# KSZ_-_ETH_HUB.net
KiCad netlist of a schematic drawn in Altium Designer
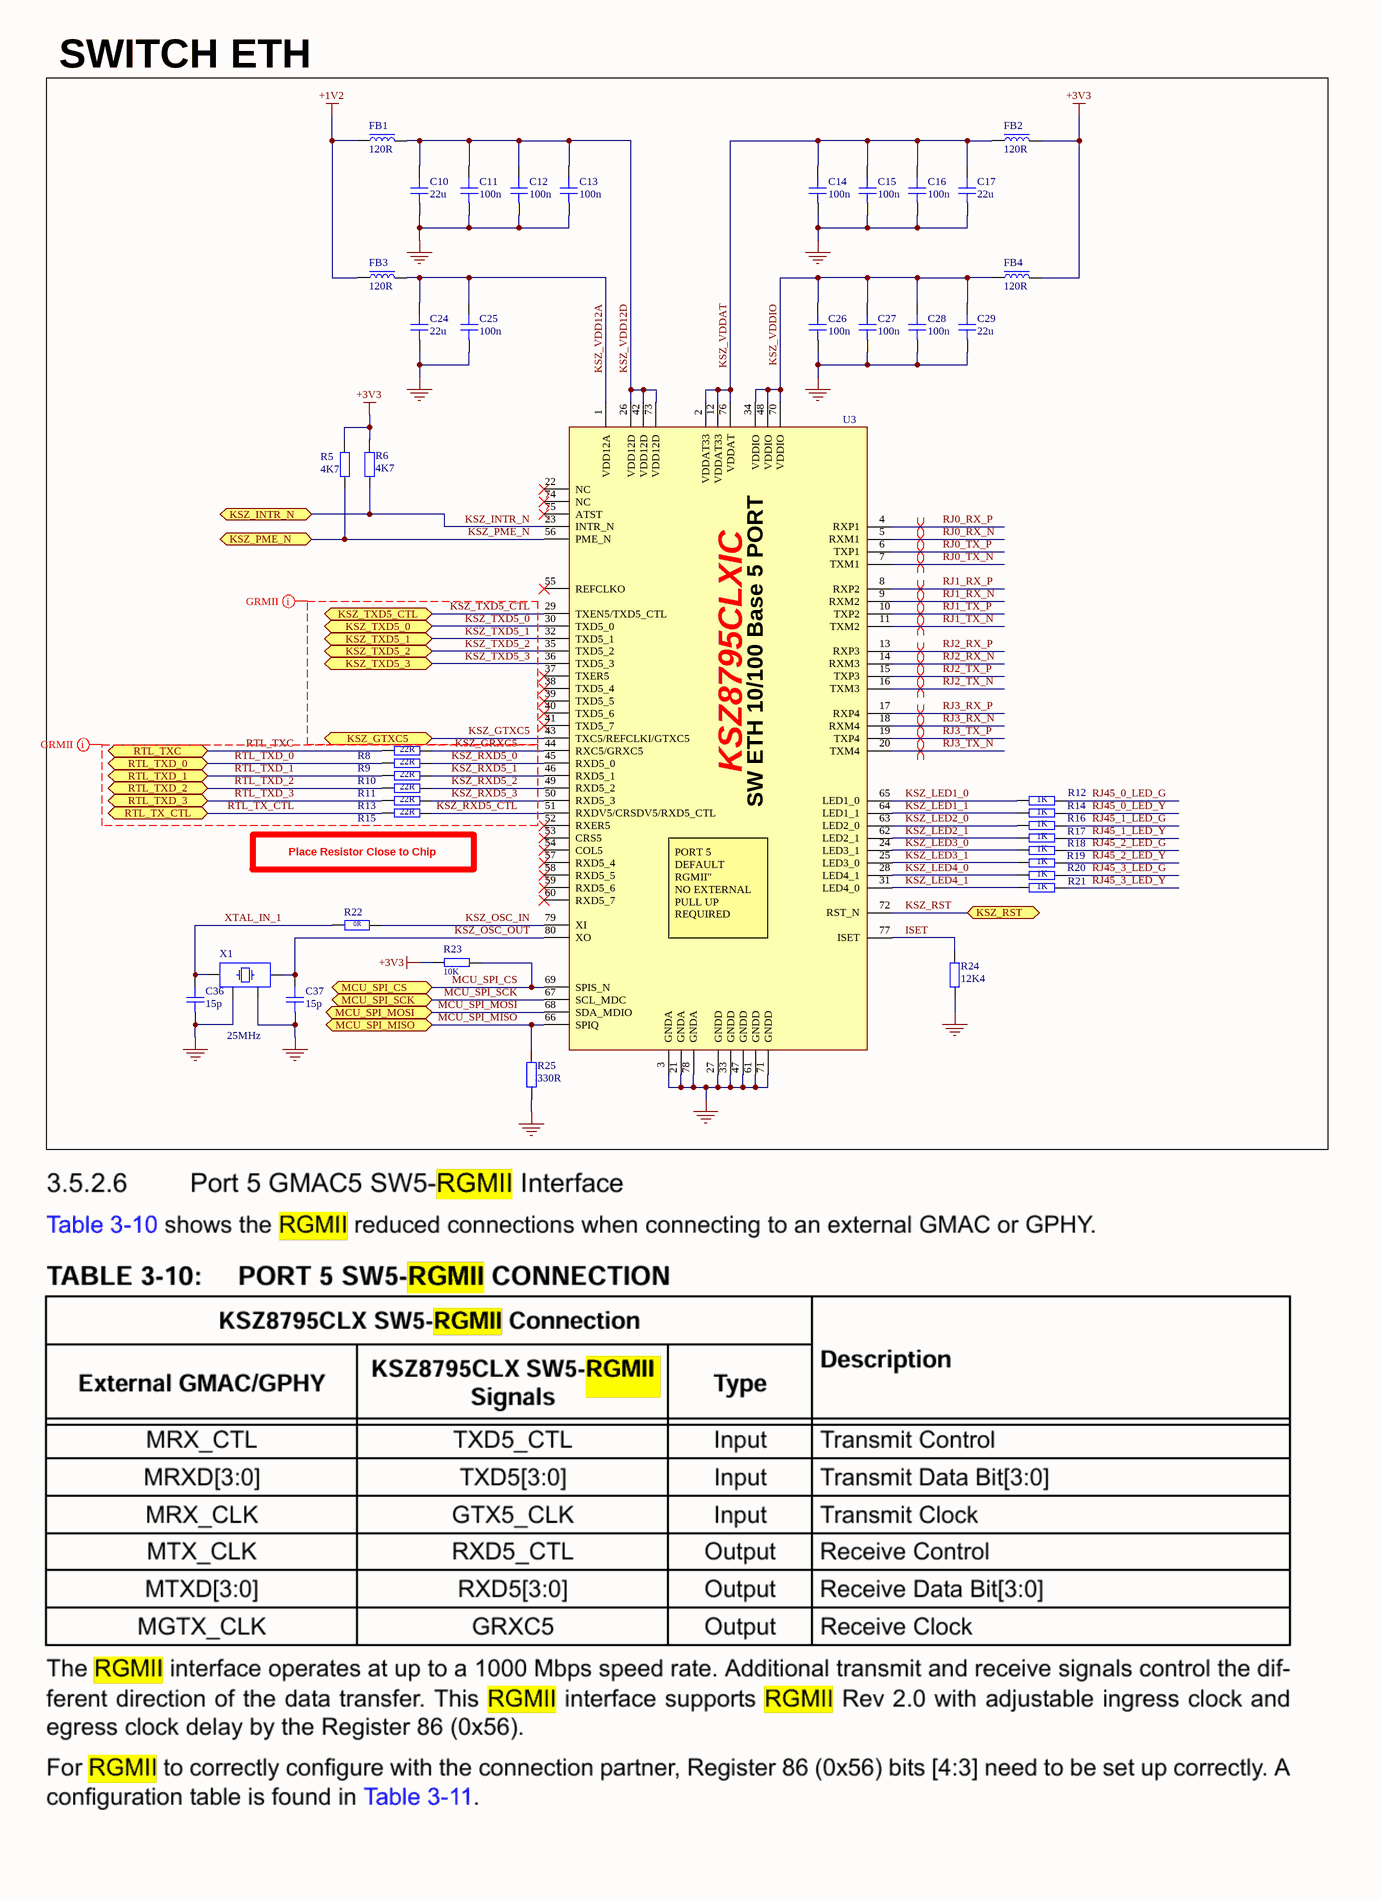
[diagram p0: KSZ - ETH HUB.SchDoc, left]
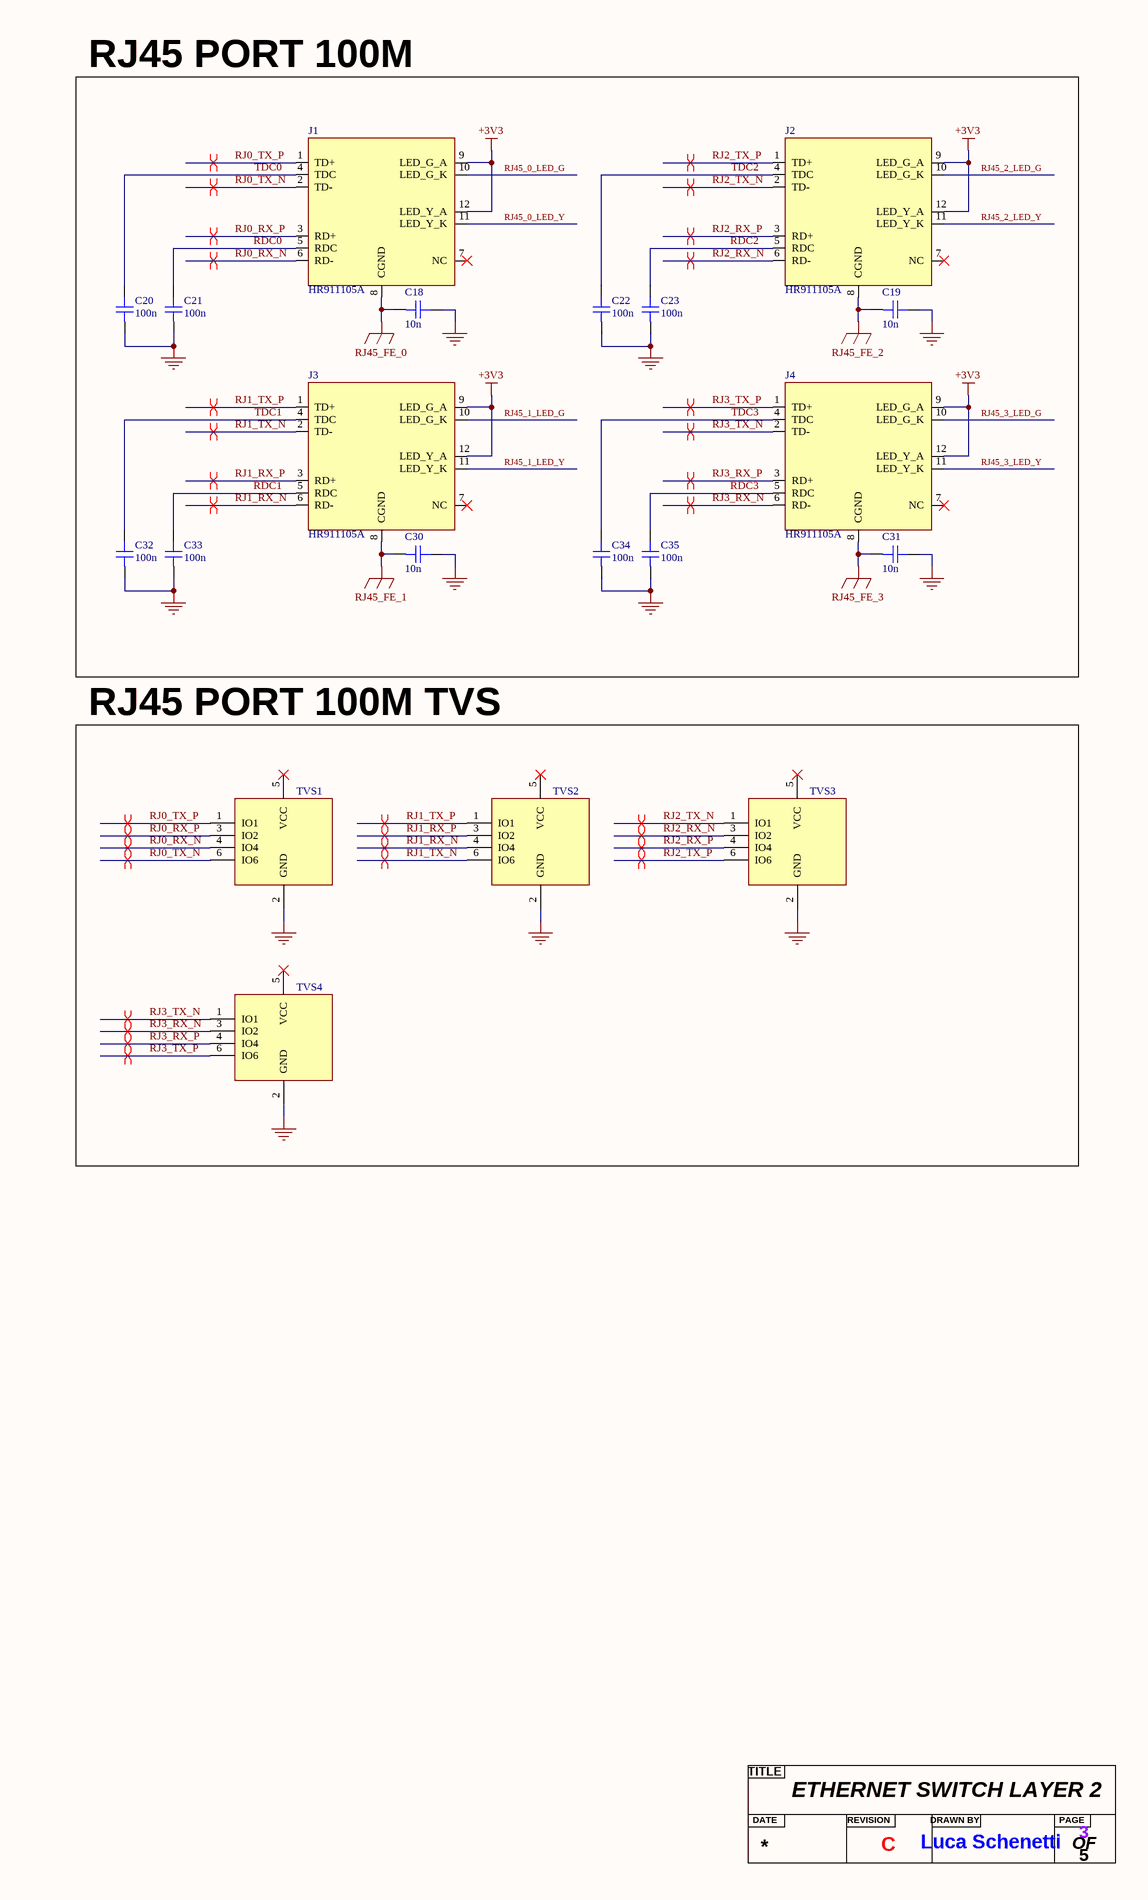
[diagram p1: KSZ - ETH HUB.SchDoc, right]

(export (version "E")
  (design (tool "Eeschema 10.0.6"))
  (components
    (comp (ref "C10")
      (value "22u")
      (footprint "CAP_0603")
      (description "Capacitor SMD 0603 [C59461]")
      (libsource (lib "Schematic-Lib-PhilsLab") (part "CAP_0603"))
    )
    (comp (ref "C11")
      (value "100n")
      (footprint "CAP_0603")
      (description "Capacitor SMD 0603 [C14663]")
      (libsource (lib "Schematic-Lib-PhilsLab") (part "CAP_0603"))
    )
    (comp (ref "C12")
      (value "100n")
      (footprint "CAP_0603")
      (description "Capacitor SMD 0603 [C14663]")
      (libsource (lib "Schematic-Lib-PhilsLab") (part "CAP_0603"))
    )
    (comp (ref "C13")
      (value "100n")
      (footprint "CAP_0603")
      (description "Capacitor SMD 0603 [C14663]")
      (libsource (lib "Schematic-Lib-PhilsLab") (part "CAP_0603"))
    )
    (comp (ref "C14")
      (value "100n")
      (footprint "CAP_0603")
      (description "Capacitor SMD 0603 [C14663]")
      (libsource (lib "Schematic-Lib-PhilsLab") (part "CAP_0603"))
    )
    (comp (ref "C15")
      (value "100n")
      (footprint "CAP_0603")
      (description "Capacitor SMD 0603 [C14663]")
      (libsource (lib "Schematic-Lib-PhilsLab") (part "CAP_0603"))
    )
    (comp (ref "C16")
      (value "100n")
      (footprint "CAP_0603")
      (description "Capacitor SMD 0603 [C14663]")
      (libsource (lib "Schematic-Lib-PhilsLab") (part "CAP_0603"))
    )
    (comp (ref "C17")
      (value "22u")
      (footprint "CAP_0603")
      (description "Capacitor SMD 0603 [C59461]")
      (libsource (lib "Schematic-Lib-PhilsLab") (part "CAP_0603"))
    )
    (comp (ref "C18")
      (value "10n")
      (footprint "CAP_1206")
      (description "[C1846]")
      (libsource (lib "Schematic-Lib-PhilsLab") (part "CAP_1206"))
    )
    (comp (ref "C19")
      (value "10n")
      (footprint "CAP_1206")
      (description "[C1846]")
      (libsource (lib "Schematic-Lib-PhilsLab") (part "CAP_1206"))
    )
    (comp (ref "C20")
      (value "100n")
      (footprint "CAP_0603")
      (description "Capacitor SMD 0603 [C14663]")
      (libsource (lib "Schematic-Lib-PhilsLab") (part "CAP_0603"))
    )
    (comp (ref "C21")
      (value "100n")
      (footprint "CAP_0603")
      (description "Capacitor SMD 0603 [C14663]")
      (libsource (lib "Schematic-Lib-PhilsLab") (part "CAP_0603"))
    )
    (comp (ref "C22")
      (value "100n")
      (footprint "CAP_0603")
      (description "Capacitor SMD 0603 [C14663]")
      (libsource (lib "Schematic-Lib-PhilsLab") (part "CAP_0603"))
    )
    (comp (ref "C23")
      (value "100n")
      (footprint "CAP_0603")
      (description "Capacitor SMD 0603 [C14663]")
      (libsource (lib "Schematic-Lib-PhilsLab") (part "CAP_0603"))
    )
    (comp (ref "C24")
      (value "22u")
      (footprint "CAP_0603")
      (description "Capacitor SMD 0603 [C59461]")
      (libsource (lib "Schematic-Lib-PhilsLab") (part "CAP_0603"))
    )
    (comp (ref "C25")
      (value "100n")
      (footprint "CAP_0603")
      (description "Capacitor SMD 0603 [C14663]")
      (libsource (lib "Schematic-Lib-PhilsLab") (part "CAP_0603"))
    )
    (comp (ref "C26")
      (value "100n")
      (footprint "CAP_0603")
      (description "Capacitor SMD 0603 [C14663]")
      (libsource (lib "Schematic-Lib-PhilsLab") (part "CAP_0603"))
    )
    (comp (ref "C27")
      (value "100n")
      (footprint "CAP_0603")
      (description "Capacitor SMD 0603 [C14663]")
      (libsource (lib "Schematic-Lib-PhilsLab") (part "CAP_0603"))
    )
    (comp (ref "C28")
      (value "100n")
      (footprint "CAP_0603")
      (description "Capacitor SMD 0603 [C14663]")
      (libsource (lib "Schematic-Lib-PhilsLab") (part "CAP_0603"))
    )
    (comp (ref "C29")
      (value "22u")
      (footprint "CAP_0603")
      (description "Capacitor SMD 0603 [C59461]")
      (libsource (lib "Schematic-Lib-PhilsLab") (part "CAP_0603"))
    )
    (comp (ref "C30")
      (value "10n")
      (footprint "CAP_1206")
      (description "[C1846]")
      (libsource (lib "Schematic-Lib-PhilsLab") (part "CAP_1206"))
    )
    (comp (ref "C31")
      (value "10n")
      (footprint "CAP_1206")
      (description "[C1846]")
      (libsource (lib "Schematic-Lib-PhilsLab") (part "CAP_1206"))
    )
    (comp (ref "C32")
      (value "100n")
      (footprint "CAP_0603")
      (description "Capacitor SMD 0603 [C14663]")
      (libsource (lib "Schematic-Lib-PhilsLab") (part "CAP_0603"))
    )
    (comp (ref "C33")
      (value "100n")
      (footprint "CAP_0603")
      (description "Capacitor SMD 0603 [C14663]")
      (libsource (lib "Schematic-Lib-PhilsLab") (part "CAP_0603"))
    )
    (comp (ref "C34")
      (value "100n")
      (footprint "CAP_0603")
      (description "Capacitor SMD 0603 [C14663]")
      (libsource (lib "Schematic-Lib-PhilsLab") (part "CAP_0603"))
    )
    (comp (ref "C35")
      (value "100n")
      (footprint "CAP_0603")
      (description "Capacitor SMD 0603 [C14663]")
      (libsource (lib "Schematic-Lib-PhilsLab") (part "CAP_0603"))
    )
    (comp (ref "C36")
      (value "15p")
      (footprint "CAP_0402")
      (description "Capacitor SMD 0402 [C1548]")
      (libsource (lib "Schematic-Lib-PhilsLab") (part "CAP_0402"))
    )
    (comp (ref "C37")
      (value "15p")
      (footprint "CAP_0402")
      (description "Capacitor SMD 0402 [C1548]")
      (libsource (lib "Schematic-Lib-PhilsLab") (part "CAP_0402"))
    )
    (comp (ref "FB1")
      (value "120R")
      (footprint "FB_0603")
      (description "Ferrite Bead SMD 0603[C76892]")
      (libsource (lib "Schematic-Lib-PhilsLab") (part "FB_0603"))
    )
    (comp (ref "FB2")
      (value "120R")
      (footprint "FB_0603")
      (description "Ferrite Bead SMD 0603[C76892]")
      (libsource (lib "Schematic-Lib-PhilsLab") (part "FB_0603"))
    )
    (comp (ref "FB3")
      (value "120R")
      (footprint "FB_0603")
      (description "Ferrite Bead SMD 0603[C76892]")
      (libsource (lib "Schematic-Lib-PhilsLab") (part "FB_0603"))
    )
    (comp (ref "FB4")
      (value "120R")
      (footprint "FB_0603")
      (description "Ferrite Bead SMD 0603[C76892]")
      (libsource (lib "Schematic-Lib-PhilsLab") (part "FB_0603"))
    )
    (comp (ref "J1")
      (value "HR911105A")
      (footprint "HR911105A")
      (description "Single Port RJ45 Connector w/ Integrated Magnetic and LED 10/100 Base-T [C12074]")
      (fields (field (name "MANUFACTURER") "HanRun"))
      (libsource (lib "Schematic-Lib-PhilsLab") (part "HR911105A"))
    )
    (comp (ref "J2")
      (value "HR911105A")
      (footprint "HR911105A")
      (description "Single Port RJ45 Connector w/ Integrated Magnetic and LED 10/100 Base-T [C12074]")
      (fields (field (name "MANUFACTURER") "HanRun"))
      (libsource (lib "Schematic-Lib-PhilsLab") (part "HR911105A"))
    )
    (comp (ref "J3")
      (value "HR911105A")
      (footprint "HR911105A")
      (description "Single Port RJ45 Connector w/ Integrated Magnetic and LED 10/100 Base-T [C12074]")
      (fields (field (name "MANUFACTURER") "HanRun"))
      (libsource (lib "Schematic-Lib-PhilsLab") (part "HR911105A"))
    )
    (comp (ref "J4")
      (value "HR911105A")
      (footprint "HR911105A")
      (description "Single Port RJ45 Connector w/ Integrated Magnetic and LED 10/100 Base-T [C12074]")
      (fields (field (name "MANUFACTURER") "HanRun"))
      (libsource (lib "Schematic-Lib-PhilsLab") (part "HR911105A"))
    )
    (comp (ref "R5")
      (value "4K7")
      (footprint "RES_0603")
      (description "[C23162]")
      (libsource (lib "Schematic-Lib-PhilsLab") (part "RES_0603"))
    )
    (comp (ref "R6")
      (value "4K7")
      (footprint "RES_0603")
      (description "[C23162]")
      (libsource (lib "Schematic-Lib-PhilsLab") (part "RES_0603"))
    )
    (comp (ref "R8")
      (value "22R")
      (footprint "RES_0402")
      (description "[C25092]")
      (libsource (lib "Schematic-Lib-PhilsLab") (part "RES_0402"))
    )
    (comp (ref "R9")
      (value "22R")
      (footprint "RES_0402")
      (description "[C25092]")
      (libsource (lib "Schematic-Lib-PhilsLab") (part "RES_0402"))
    )
    (comp (ref "R10")
      (value "22R")
      (footprint "RES_0402")
      (description "[C25092]")
      (libsource (lib "Schematic-Lib-PhilsLab") (part "RES_0402"))
    )
    (comp (ref "R11")
      (value "22R")
      (footprint "RES_0402")
      (description "[C25092]")
      (libsource (lib "Schematic-Lib-PhilsLab") (part "RES_0402"))
    )
    (comp (ref "R12")
      (value "1K")
      (footprint "RES_0603")
      (description "[C21190]")
      (libsource (lib "Schematic-Lib-PhilsLab") (part "RES_0603"))
    )
    (comp (ref "R13")
      (value "22R")
      (footprint "RES_0402")
      (description "[C25092]")
      (libsource (lib "Schematic-Lib-PhilsLab") (part "RES_0402"))
    )
    (comp (ref "R14")
      (value "1K")
      (footprint "RES_0603")
      (description "[C21190]")
      (libsource (lib "Schematic-Lib-PhilsLab") (part "RES_0603"))
    )
    (comp (ref "R15")
      (value "22R")
      (footprint "RES_0402")
      (description "[C25092]")
      (libsource (lib "Schematic-Lib-PhilsLab") (part "RES_0402"))
    )
    (comp (ref "R16")
      (value "1K")
      (footprint "RES_0603")
      (description "[C21190]")
      (libsource (lib "Schematic-Lib-PhilsLab") (part "RES_0603"))
    )
    (comp (ref "R17")
      (value "1K")
      (footprint "RES_0603")
      (description "[C21190]")
      (libsource (lib "Schematic-Lib-PhilsLab") (part "RES_0603"))
    )
    (comp (ref "R18")
      (value "1K")
      (footprint "RES_0603")
      (description "[C21190]")
      (libsource (lib "Schematic-Lib-PhilsLab") (part "RES_0603"))
    )
    (comp (ref "R19")
      (value "1K")
      (footprint "RES_0603")
      (description "[C21190]")
      (libsource (lib "Schematic-Lib-PhilsLab") (part "RES_0603"))
    )
    (comp (ref "R20")
      (value "1K")
      (footprint "RES_0603")
      (description "[C21190]")
      (libsource (lib "Schematic-Lib-PhilsLab") (part "RES_0603"))
    )
    (comp (ref "R21")
      (value "1K")
      (footprint "RES_0603")
      (description "[C21190]")
      (libsource (lib "Schematic-Lib-PhilsLab") (part "RES_0603"))
    )
    (comp (ref "R22")
      (value "0R")
      (footprint "RES_0402")
      (description "Resistor SMD 0402 [C17168]")
      (libsource (lib "Schematic-Lib-PhilsLab") (part "RES_0402"))
    )
    (comp (ref "R23")
      (value "10K")
      (footprint "RES_0603")
      (description "[C25804]")
      (libsource (lib "Schematic-Lib-PhilsLab") (part "RES_0603"))
    )
    (comp (ref "R24")
      (value "12K4")
      (footprint "RES_0603")
      (description "[C22865]")
      (libsource (lib "Schematic-Lib-PhilsLab") (part "RES_0603"))
    )
    (comp (ref "R25")
      (value "330R")
      (footprint "RES_0603")
      (description "[C23138]")
      (libsource (lib "Schematic-Lib-PhilsLab") (part "RES_0603"))
    )
    (comp (ref "TVS1")
      (value "ESD 5A 75W 12.5V 6V Bidirectional 5V")
      (footprint "SRV05-4")
      (description "[C7420376]")
      (libsource (lib "My_Library") (part "SRV05-4"))
    )
    (comp (ref "TVS2")
      (value "ESD 5A 75W 12.5V 6V Bidirectional 5V")
      (footprint "SRV05-4")
      (description "[C7420376]")
      (libsource (lib "My_Library") (part "SRV05-4"))
    )
    (comp (ref "TVS3")
      (value "ESD 5A 75W 12.5V 6V Bidirectional 5V")
      (footprint "SRV05-4")
      (description "[C7420376]")
      (libsource (lib "My_Library") (part "SRV05-4"))
    )
    (comp (ref "TVS4")
      (value "ESD 5A 75W 12.5V 6V Bidirectional 5V")
      (footprint "SRV05-4")
      (description "[C7420376]")
      (libsource (lib "My_Library") (part "SRV05-4"))
    )
    (comp (ref "U3")
      (value "5-Port 10/100-Man Eth")
      (footprint "KSZ8795CLXIC")
      (description "[C69416]")
      (libsource (lib "My_Library") (part "KSZ8795CLXIC"))
    )
    (comp (ref "X1")
      (value "25MHz")
      (footprint "XTAL_3225")
      (description "Crystal SMD 24MHz 10PPM 7pF 3225 [C9006]")
      (fields
        (field (name "MANUFACTURER") "Epson")
        (field (name "MANUFACTURER PART NUMBER") "TSX-3225 24.0000MF15X-AC")
      )
      (libsource (lib "Schematic-Lib-PhilsLab") (part "TSX-3225_24.0000MF15X-AC"))
    )
  )
  (nets
    (net (code "1") (name "+1V2") (class "Default")
      (node (ref "FB1") (pin "1") (pinfunction "1_1") (pintype "passive"))
      (node (ref "FB3") (pin "1") (pinfunction "1_1") (pintype "passive"))
    )
    (net (code "2") (name "+3V3") (class "Default")
      (node (ref "FB2") (pin "2") (pinfunction "2_2") (pintype "passive"))
      (node (ref "FB4") (pin "2") (pinfunction "2_2") (pintype "passive"))
      (node (ref "J1") (pin "12") (pinfunction "LED_Y_A_12") (pintype "passive"))
      (node (ref "J1") (pin "9") (pinfunction "LED_G_A_9") (pintype "passive"))
      (node (ref "J2") (pin "12") (pinfunction "LED_Y_A_12") (pintype "passive"))
      (node (ref "J2") (pin "9") (pinfunction "LED_G_A_9") (pintype "passive"))
      (node (ref "J3") (pin "12") (pinfunction "LED_Y_A_12") (pintype "passive"))
      (node (ref "J3") (pin "9") (pinfunction "LED_G_A_9") (pintype "passive"))
      (node (ref "J4") (pin "12") (pinfunction "LED_Y_A_12") (pintype "passive"))
      (node (ref "J4") (pin "9") (pinfunction "LED_G_A_9") (pintype "passive"))
      (node (ref "R23") (pin "2") (pinfunction "2_2") (pintype "passive"))
      (node (ref "R5") (pin "2") (pinfunction "2_2") (pintype "passive"))
      (node (ref "R6") (pin "2") (pinfunction "2_2") (pintype "passive"))
    )
    (net (code "3") (name "/ISET") (class "Default")
      (node (ref "R24") (pin "2") (pinfunction "2_2") (pintype "passive"))
      (node (ref "U3") (pin "77") (pinfunction "ISET_77") (pintype "passive"))
    )
    (net (code "4") (name "/KSZ_GRXC5") (class "Default")
      (node (ref "R8") (pin "2") (pinfunction "2_2") (pintype "passive"))
      (node (ref "U3") (pin "44") (pinfunction "RXC5/GRXC5_44") (pintype "passive"))
    )
    (net (code "5") (name "/KSZ_GTXC5") (class "Default")
      (node (ref "U3") (pin "43") (pinfunction "TXC5/REFCLKI/GTXC5_43") (pintype "passive"))
    )
    (net (code "6") (name "/KSZ_INTR_N") (class "Default")
      (node (ref "R6") (pin "1") (pinfunction "1_1") (pintype "passive"))
      (node (ref "U3") (pin "23") (pinfunction "INTR_N_23") (pintype "passive"))
    )
    (net (code "7") (name "/KSZ_LED1_0") (class "Default")
      (node (ref "R14") (pin "2") (pinfunction "2_2") (pintype "passive"))
      (node (ref "U3") (pin "65") (pinfunction "LED1_0_65") (pintype "passive"))
    )
    (net (code "8") (name "/KSZ_LED1_1") (class "Default")
      (node (ref "R12") (pin "2") (pinfunction "2_2") (pintype "passive"))
      (node (ref "U3") (pin "64") (pinfunction "LED1_1_64") (pintype "passive"))
    )
    (net (code "9") (name "/KSZ_LED2_0") (class "Default")
      (node (ref "R16") (pin "2") (pinfunction "2_2") (pintype "passive"))
      (node (ref "U3") (pin "63") (pinfunction "LED2_0_63") (pintype "passive"))
    )
    (net (code "10") (name "/KSZ_LED2_1") (class "Default")
      (node (ref "R17") (pin "2") (pinfunction "2_2") (pintype "passive"))
      (node (ref "U3") (pin "62") (pinfunction "LED2_1_62") (pintype "passive"))
    )
    (net (code "11") (name "/KSZ_LED3_0") (class "Default")
      (node (ref "R18") (pin "2") (pinfunction "2_2") (pintype "passive"))
      (node (ref "U3") (pin "24") (pinfunction "LED3_1_24") (pintype "passive"))
    )
    (net (code "12") (name "/KSZ_LED3_1") (class "Default")
      (node (ref "R19") (pin "2") (pinfunction "2_2") (pintype "passive"))
      (node (ref "U3") (pin "25") (pinfunction "LED3_0_25") (pintype "passive"))
    )
    (net (code "13") (name "/KSZ_LED4_0") (class "Default")
      (node (ref "R20") (pin "2") (pinfunction "2_2") (pintype "passive"))
      (node (ref "U3") (pin "28") (pinfunction "LED4_1_28") (pintype "passive"))
    )
    (net (code "14") (name "/KSZ_LED4_1") (class "Default")
      (node (ref "R21") (pin "2") (pinfunction "2_2") (pintype "passive"))
      (node (ref "U3") (pin "31") (pinfunction "LED4_0_31") (pintype "passive"))
    )
    (net (code "15") (name "/KSZ_OSC_IN") (class "Default")
      (node (ref "R22") (pin "2") (pinfunction "2_2") (pintype "passive"))
      (node (ref "U3") (pin "79") (pinfunction "XI_79") (pintype "passive"))
    )
    (net (code "16") (name "/KSZ_OSC_OUT") (class "Default")
      (node (ref "C37") (pin "2") (pinfunction "2_2") (pintype "passive"))
      (node (ref "U3") (pin "80") (pinfunction "XO_80") (pintype "passive"))
      (node (ref "X1") (pin "1") (pinfunction "1_1") (pintype "passive"))
    )
    (net (code "17") (name "/KSZ_PME_N") (class "Default")
      (node (ref "R5") (pin "1") (pinfunction "1_1") (pintype "passive"))
      (node (ref "U3") (pin "56") (pinfunction "PME_N_56") (pintype "passive"))
    )
    (net (code "18") (name "/KSZ_RST") (class "Default")
      (node (ref "U3") (pin "72") (pinfunction "RST_N_72") (pintype "passive"))
    )
    (net (code "19") (name "/KSZ_RXD5_0") (class "Default")
      (node (ref "R9") (pin "2") (pinfunction "2_2") (pintype "passive"))
      (node (ref "U3") (pin "45") (pinfunction "RXD5_0_45") (pintype "passive"))
    )
    (net (code "20") (name "/KSZ_RXD5_1") (class "Default")
      (node (ref "R10") (pin "2") (pinfunction "2_2") (pintype "passive"))
      (node (ref "U3") (pin "46") (pinfunction "RXD5_1_46") (pintype "passive"))
    )
    (net (code "21") (name "/KSZ_RXD5_2") (class "Default")
      (node (ref "R11") (pin "2") (pinfunction "2_2") (pintype "passive"))
      (node (ref "U3") (pin "49") (pinfunction "RXD5_2_49") (pintype "passive"))
    )
    (net (code "22") (name "/KSZ_RXD5_3") (class "Default")
      (node (ref "R13") (pin "2") (pinfunction "2_2") (pintype "passive"))
      (node (ref "U3") (pin "50") (pinfunction "RXD5_3_50") (pintype "passive"))
    )
    (net (code "23") (name "/KSZ_RXD5_CTL") (class "Default")
      (node (ref "R15") (pin "2") (pinfunction "2_2") (pintype "passive"))
      (node (ref "U3") (pin "51") (pinfunction "RXDV5/CRSDV5/RXD5_CTL_51") (pintype "passive"))
    )
    (net (code "24") (name "/KSZ_TXD5_0") (class "Default")
      (node (ref "U3") (pin "30") (pinfunction "TXD5_0_30") (pintype "passive"))
    )
    (net (code "25") (name "/KSZ_TXD5_1") (class "Default")
      (node (ref "U3") (pin "32") (pinfunction "TXD5_1_32") (pintype "passive"))
    )
    (net (code "26") (name "/KSZ_TXD5_2") (class "Default")
      (node (ref "U3") (pin "35") (pinfunction "TXD5_2_35") (pintype "passive"))
    )
    (net (code "27") (name "/KSZ_TXD5_3") (class "Default")
      (node (ref "U3") (pin "36") (pinfunction "TXD5_3_36") (pintype "passive"))
    )
    (net (code "28") (name "/KSZ_TXD5_CTL") (class "Default")
      (node (ref "U3") (pin "29") (pinfunction "TXEN5/TXD5_CTL_29") (pintype "passive"))
    )
    (net (code "29") (name "/KSZ_VDD12A") (class "Default")
      (node (ref "C24") (pin "2") (pinfunction "2_2") (pintype "passive"))
      (node (ref "C25") (pin "2") (pinfunction "2_2") (pintype "passive"))
      (node (ref "FB3") (pin "2") (pinfunction "2_2") (pintype "passive"))
      (node (ref "U3") (pin "1") (pinfunction "VDD12A_1") (pintype "passive"))
    )
    (net (code "30") (name "/KSZ_VDD12D") (class "Default")
      (node (ref "C10") (pin "2") (pinfunction "2_2") (pintype "passive"))
      (node (ref "C11") (pin "2") (pinfunction "2_2") (pintype "passive"))
      (node (ref "C12") (pin "2") (pinfunction "2_2") (pintype "passive"))
      (node (ref "C13") (pin "2") (pinfunction "2_2") (pintype "passive"))
      (node (ref "FB1") (pin "2") (pinfunction "2_2") (pintype "passive"))
      (node (ref "U3") (pin "26") (pinfunction "VDD12D_26") (pintype "passive"))
      (node (ref "U3") (pin "42") (pinfunction "VDD12D_42") (pintype "passive"))
      (node (ref "U3") (pin "73") (pinfunction "VDD12D_73") (pintype "passive"))
    )
    (net (code "31") (name "/KSZ_VDDAT") (class "Default")
      (node (ref "C14") (pin "2") (pinfunction "2_2") (pintype "passive"))
      (node (ref "C15") (pin "2") (pinfunction "2_2") (pintype "passive"))
      (node (ref "C16") (pin "2") (pinfunction "2_2") (pintype "passive"))
      (node (ref "C17") (pin "2") (pinfunction "2_2") (pintype "passive"))
      (node (ref "FB2") (pin "1") (pinfunction "1_1") (pintype "passive"))
      (node (ref "U3") (pin "12") (pinfunction "VDDAT33_12") (pintype "passive"))
      (node (ref "U3") (pin "2") (pinfunction "VDDAT33_2") (pintype "passive"))
      (node (ref "U3") (pin "76") (pinfunction "VDDAT_76") (pintype "passive"))
    )
    (net (code "32") (name "/KSZ_VDDIO") (class "Default")
      (node (ref "C26") (pin "2") (pinfunction "2_2") (pintype "passive"))
      (node (ref "C27") (pin "2") (pinfunction "2_2") (pintype "passive"))
      (node (ref "C28") (pin "2") (pinfunction "2_2") (pintype "passive"))
      (node (ref "C29") (pin "2") (pinfunction "2_2") (pintype "passive"))
      (node (ref "FB4") (pin "1") (pinfunction "1_1") (pintype "passive"))
      (node (ref "U3") (pin "34") (pinfunction "VDDIO_34") (pintype "passive"))
      (node (ref "U3") (pin "48") (pinfunction "VDDIO_48") (pintype "passive"))
      (node (ref "U3") (pin "70") (pinfunction "VDDIO_70") (pintype "passive"))
    )
    (net (code "33") (name "/MCU_SPI_CS") (class "Default")
      (node (ref "R23") (pin "1") (pinfunction "1_1") (pintype "passive"))
      (node (ref "U3") (pin "69") (pinfunction "SPIS_N_69") (pintype "passive"))
    )
    (net (code "34") (name "/MCU_SPI_MISO") (class "Default")
      (node (ref "R25") (pin "2") (pinfunction "2_2") (pintype "passive"))
      (node (ref "U3") (pin "66") (pinfunction "SPIQ_66") (pintype "passive"))
    )
    (net (code "35") (name "/MCU_SPI_MOSI") (class "Default")
      (node (ref "U3") (pin "68") (pinfunction "SDA_MDIO_68") (pintype "passive"))
    )
    (net (code "36") (name "/MCU_SPI_SCK") (class "Default")
      (node (ref "U3") (pin "67") (pinfunction "SCL_MDC_67") (pintype "passive"))
    )
    (net (code "37") (name "/RDC0") (class "Default")
      (node (ref "C21") (pin "2") (pinfunction "2_2") (pintype "passive"))
      (node (ref "J1") (pin "5") (pinfunction "RDC_5") (pintype "passive"))
    )
    (net (code "38") (name "/RDC1") (class "Default")
      (node (ref "C33") (pin "2") (pinfunction "2_2") (pintype "passive"))
      (node (ref "J3") (pin "5") (pinfunction "RDC_5") (pintype "passive"))
    )
    (net (code "39") (name "/RDC2") (class "Default")
      (node (ref "C23") (pin "2") (pinfunction "2_2") (pintype "passive"))
      (node (ref "J2") (pin "5") (pinfunction "RDC_5") (pintype "passive"))
    )
    (net (code "40") (name "/RDC3") (class "Default")
      (node (ref "C35") (pin "2") (pinfunction "2_2") (pintype "passive"))
      (node (ref "J4") (pin "5") (pinfunction "RDC_5") (pintype "passive"))
    )
    (net (code "41") (name "/RJ0_RX_N") (class "Default")
      (node (ref "J1") (pin "6") (pinfunction "RD-_6") (pintype "passive"))
      (node (ref "TVS1") (pin "4") (pinfunction "IO4_4") (pintype "passive"))
      (node (ref "U3") (pin "5") (pinfunction "RXM1_5") (pintype "passive"))
    )
    (net (code "42") (name "/RJ0_RX_P") (class "Default")
      (node (ref "J1") (pin "3") (pinfunction "RD+_3") (pintype "passive"))
      (node (ref "TVS1") (pin "3") (pinfunction "IO2_3") (pintype "passive"))
      (node (ref "U3") (pin "4") (pinfunction "RXP1_4") (pintype "passive"))
    )
    (net (code "43") (name "/RJ0_TX_N") (class "Default")
      (node (ref "J1") (pin "2") (pinfunction "TD-_2") (pintype "passive"))
      (node (ref "TVS1") (pin "6") (pinfunction "IO6_6") (pintype "passive"))
      (node (ref "U3") (pin "7") (pinfunction "TXM1_7") (pintype "passive"))
    )
    (net (code "44") (name "/RJ0_TX_P") (class "Default")
      (node (ref "J1") (pin "1") (pinfunction "TD+_1") (pintype "passive"))
      (node (ref "TVS1") (pin "1") (pinfunction "IO1_1") (pintype "passive"))
      (node (ref "U3") (pin "6") (pinfunction "TXP1_6") (pintype "passive"))
    )
    (net (code "45") (name "/RJ1_RX_N") (class "Default")
      (node (ref "J3") (pin "6") (pinfunction "RD-_6") (pintype "passive"))
      (node (ref "TVS2") (pin "4") (pinfunction "IO4_4") (pintype "passive"))
      (node (ref "U3") (pin "9") (pinfunction "RXM2_9") (pintype "passive"))
    )
    (net (code "46") (name "/RJ1_RX_P") (class "Default")
      (node (ref "J3") (pin "3") (pinfunction "RD+_3") (pintype "passive"))
      (node (ref "TVS2") (pin "3") (pinfunction "IO2_3") (pintype "passive"))
      (node (ref "U3") (pin "8") (pinfunction "RXP2_8") (pintype "passive"))
    )
    (net (code "47") (name "/RJ1_TX_N") (class "Default")
      (node (ref "J3") (pin "2") (pinfunction "TD-_2") (pintype "passive"))
      (node (ref "TVS2") (pin "6") (pinfunction "IO6_6") (pintype "passive"))
      (node (ref "U3") (pin "11") (pinfunction "TXM2_11") (pintype "passive"))
    )
    (net (code "48") (name "/RJ1_TX_P") (class "Default")
      (node (ref "J3") (pin "1") (pinfunction "TD+_1") (pintype "passive"))
      (node (ref "TVS2") (pin "1") (pinfunction "IO1_1") (pintype "passive"))
      (node (ref "U3") (pin "10") (pinfunction "TXP2_10") (pintype "passive"))
    )
    (net (code "49") (name "/RJ2_RX_N") (class "Default")
      (node (ref "J2") (pin "6") (pinfunction "RD-_6") (pintype "passive"))
      (node (ref "TVS3") (pin "3") (pinfunction "IO2_3") (pintype "passive"))
      (node (ref "U3") (pin "14") (pinfunction "RXM3_14") (pintype "passive"))
    )
    (net (code "50") (name "/RJ2_RX_P") (class "Default")
      (node (ref "J2") (pin "3") (pinfunction "RD+_3") (pintype "passive"))
      (node (ref "TVS3") (pin "4") (pinfunction "IO4_4") (pintype "passive"))
      (node (ref "U3") (pin "13") (pinfunction "RXP3_13") (pintype "passive"))
    )
    (net (code "51") (name "/RJ2_TX_N") (class "Default")
      (node (ref "J2") (pin "2") (pinfunction "TD-_2") (pintype "passive"))
      (node (ref "TVS3") (pin "1") (pinfunction "IO1_1") (pintype "passive"))
      (node (ref "U3") (pin "16") (pinfunction "TXM3_16") (pintype "passive"))
    )
    (net (code "52") (name "/RJ2_TX_P") (class "Default")
      (node (ref "J2") (pin "1") (pinfunction "TD+_1") (pintype "passive"))
      (node (ref "TVS3") (pin "6") (pinfunction "IO6_6") (pintype "passive"))
      (node (ref "U3") (pin "15") (pinfunction "TXP3_15") (pintype "passive"))
    )
    (net (code "53") (name "/RJ3_RX_N") (class "Default")
      (node (ref "J4") (pin "6") (pinfunction "RD-_6") (pintype "passive"))
      (node (ref "TVS4") (pin "3") (pinfunction "IO2_3") (pintype "passive"))
      (node (ref "U3") (pin "18") (pinfunction "RXM4_18") (pintype "passive"))
    )
    (net (code "54") (name "/RJ3_RX_P") (class "Default")
      (node (ref "J4") (pin "3") (pinfunction "RD+_3") (pintype "passive"))
      (node (ref "TVS4") (pin "4") (pinfunction "IO4_4") (pintype "passive"))
      (node (ref "U3") (pin "17") (pinfunction "RXP4_17") (pintype "passive"))
    )
    (net (code "55") (name "/RJ3_TX_N") (class "Default")
      (node (ref "J4") (pin "2") (pinfunction "TD-_2") (pintype "passive"))
      (node (ref "TVS4") (pin "1") (pinfunction "IO1_1") (pintype "passive"))
      (node (ref "U3") (pin "20") (pinfunction "TXM4_20") (pintype "passive"))
    )
    (net (code "56") (name "/RJ3_TX_P") (class "Default")
      (node (ref "J4") (pin "1") (pinfunction "TD+_1") (pintype "passive"))
      (node (ref "TVS4") (pin "6") (pinfunction "IO6_6") (pintype "passive"))
      (node (ref "U3") (pin "19") (pinfunction "TXP4_19") (pintype "passive"))
    )
    (net (code "57") (name "/RJ45_0_LED_G") (class "Default")
      (node (ref "J1") (pin "10") (pinfunction "LED_G_K_10") (pintype "passive"))
      (node (ref "R14") (pin "1") (pinfunction "1_1") (pintype "passive"))
    )
    (net (code "58") (name "/RJ45_0_LED_Y") (class "Default")
      (node (ref "J1") (pin "11") (pinfunction "LED_Y_K_11") (pintype "passive"))
      (node (ref "R12") (pin "1") (pinfunction "1_1") (pintype "passive"))
    )
    (net (code "59") (name "/RJ45_1_LED_G") (class "Default")
      (node (ref "J3") (pin "10") (pinfunction "LED_G_K_10") (pintype "passive"))
      (node (ref "R16") (pin "1") (pinfunction "1_1") (pintype "passive"))
    )
    (net (code "60") (name "/RJ45_1_LED_Y") (class "Default")
      (node (ref "J3") (pin "11") (pinfunction "LED_Y_K_11") (pintype "passive"))
      (node (ref "R17") (pin "1") (pinfunction "1_1") (pintype "passive"))
    )
    (net (code "61") (name "/RJ45_2_LED_G") (class "Default")
      (node (ref "J2") (pin "10") (pinfunction "LED_G_K_10") (pintype "passive"))
      (node (ref "R18") (pin "1") (pinfunction "1_1") (pintype "passive"))
    )
    (net (code "62") (name "/RJ45_2_LED_Y") (class "Default")
      (node (ref "J2") (pin "11") (pinfunction "LED_Y_K_11") (pintype "passive"))
      (node (ref "R19") (pin "1") (pinfunction "1_1") (pintype "passive"))
    )
    (net (code "63") (name "/RJ45_3_LED_G") (class "Default")
      (node (ref "J4") (pin "10") (pinfunction "LED_G_K_10") (pintype "passive"))
      (node (ref "R20") (pin "1") (pinfunction "1_1") (pintype "passive"))
    )
    (net (code "64") (name "/RJ45_3_LED_Y") (class "Default")
      (node (ref "J4") (pin "11") (pinfunction "LED_Y_K_11") (pintype "passive"))
      (node (ref "R21") (pin "1") (pinfunction "1_1") (pintype "passive"))
    )
    (net (code "65") (name "/RTL_TXC") (class "Default")
      (node (ref "R8") (pin "1") (pinfunction "1_1") (pintype "passive"))
    )
    (net (code "66") (name "/RTL_TXD_0") (class "Default")
      (node (ref "R9") (pin "1") (pinfunction "1_1") (pintype "passive"))
    )
    (net (code "67") (name "/RTL_TXD_1") (class "Default")
      (node (ref "R10") (pin "1") (pinfunction "1_1") (pintype "passive"))
    )
    (net (code "68") (name "/RTL_TXD_2") (class "Default")
      (node (ref "R11") (pin "1") (pinfunction "1_1") (pintype "passive"))
    )
    (net (code "69") (name "/RTL_TXD_3") (class "Default")
      (node (ref "R13") (pin "1") (pinfunction "1_1") (pintype "passive"))
    )
    (net (code "70") (name "/RTL_TX_CTL") (class "Default")
      (node (ref "R15") (pin "1") (pinfunction "1_1") (pintype "passive"))
    )
    (net (code "71") (name "/TDC0") (class "Default")
      (node (ref "C20") (pin "2") (pinfunction "2_2") (pintype "passive"))
      (node (ref "J1") (pin "4") (pinfunction "TDC_4") (pintype "passive"))
    )
    (net (code "72") (name "/TDC1") (class "Default")
      (node (ref "C32") (pin "2") (pinfunction "2_2") (pintype "passive"))
      (node (ref "J3") (pin "4") (pinfunction "TDC_4") (pintype "passive"))
    )
    (net (code "73") (name "/TDC2") (class "Default")
      (node (ref "C22") (pin "2") (pinfunction "2_2") (pintype "passive"))
      (node (ref "J2") (pin "4") (pinfunction "TDC_4") (pintype "passive"))
    )
    (net (code "74") (name "/TDC3") (class "Default")
      (node (ref "C34") (pin "2") (pinfunction "2_2") (pintype "passive"))
      (node (ref "J4") (pin "4") (pinfunction "TDC_4") (pintype "passive"))
    )
    (net (code "75") (name "/XTAL_IN_1") (class "Default")
      (node (ref "C36") (pin "2") (pinfunction "2_2") (pintype "passive"))
      (node (ref "R22") (pin "1") (pinfunction "1_1") (pintype "passive"))
      (node (ref "X1") (pin "3") (pinfunction "3_3") (pintype "passive"))
    )
    (net (code "76") (name "GND") (class "Default")
      (node (ref "C10") (pin "1") (pinfunction "1_1") (pintype "passive"))
      (node (ref "C11") (pin "1") (pinfunction "1_1") (pintype "passive"))
      (node (ref "C12") (pin "1") (pinfunction "1_1") (pintype "passive"))
      (node (ref "C13") (pin "1") (pinfunction "1_1") (pintype "passive"))
      (node (ref "C14") (pin "1") (pinfunction "1_1") (pintype "passive"))
      (node (ref "C15") (pin "1") (pinfunction "1_1") (pintype "passive"))
      (node (ref "C16") (pin "1") (pinfunction "1_1") (pintype "passive"))
      (node (ref "C17") (pin "1") (pinfunction "1_1") (pintype "passive"))
      (node (ref "C18") (pin "2") (pinfunction "2_2") (pintype "passive"))
      (node (ref "C19") (pin "2") (pinfunction "2_2") (pintype "passive"))
      (node (ref "C20") (pin "1") (pinfunction "1_1") (pintype "passive"))
      (node (ref "C21") (pin "1") (pinfunction "1_1") (pintype "passive"))
      (node (ref "C22") (pin "1") (pinfunction "1_1") (pintype "passive"))
      (node (ref "C23") (pin "1") (pinfunction "1_1") (pintype "passive"))
      (node (ref "C24") (pin "1") (pinfunction "1_1") (pintype "passive"))
      (node (ref "C25") (pin "1") (pinfunction "1_1") (pintype "passive"))
      (node (ref "C26") (pin "1") (pinfunction "1_1") (pintype "passive"))
      (node (ref "C27") (pin "1") (pinfunction "1_1") (pintype "passive"))
      (node (ref "C28") (pin "1") (pinfunction "1_1") (pintype "passive"))
      (node (ref "C29") (pin "1") (pinfunction "1_1") (pintype "passive"))
      (node (ref "C30") (pin "2") (pinfunction "2_2") (pintype "passive"))
      (node (ref "C31") (pin "2") (pinfunction "2_2") (pintype "passive"))
      (node (ref "C32") (pin "1") (pinfunction "1_1") (pintype "passive"))
      (node (ref "C33") (pin "1") (pinfunction "1_1") (pintype "passive"))
      (node (ref "C34") (pin "1") (pinfunction "1_1") (pintype "passive"))
      (node (ref "C35") (pin "1") (pinfunction "1_1") (pintype "passive"))
      (node (ref "C36") (pin "1") (pinfunction "1_1") (pintype "passive"))
      (node (ref "C37") (pin "1") (pinfunction "1_1") (pintype "passive"))
      (node (ref "R24") (pin "1") (pinfunction "1_1") (pintype "passive"))
      (node (ref "R25") (pin "1") (pinfunction "1_1") (pintype "passive"))
      (node (ref "TVS1") (pin "2") (pinfunction "GND_2") (pintype "power_in"))
      (node (ref "TVS2") (pin "2") (pinfunction "GND_2") (pintype "power_in"))
      (node (ref "TVS3") (pin "2") (pinfunction "GND_2") (pintype "power_in"))
      (node (ref "TVS4") (pin "2") (pinfunction "GND_2") (pintype "power_in"))
      (node (ref "U3") (pin "21") (pinfunction "GNDA_21") (pintype "power_in"))
      (node (ref "U3") (pin "27") (pinfunction "GNDD_27") (pintype "power_in"))
      (node (ref "U3") (pin "3") (pinfunction "GNDA_3") (pintype "power_in"))
      (node (ref "U3") (pin "33") (pinfunction "GNDD_33") (pintype "power_in"))
      (node (ref "U3") (pin "47") (pinfunction "GNDD_47") (pintype "power_in"))
      (node (ref "U3") (pin "61") (pinfunction "GNDD_61") (pintype "power_in"))
      (node (ref "U3") (pin "71") (pinfunction "GNDD_71") (pintype "power_in"))
      (node (ref "U3") (pin "78") (pinfunction "GNDA_78") (pintype "power_in"))
      (node (ref "X1") (pin "2") (pinfunction "2_2") (pintype "passive"))
      (node (ref "X1") (pin "4") (pinfunction "4_4") (pintype "passive"))
    )
    (net (code "77") (name "RJ45_FE_0") (class "Default")
      (node (ref "C18") (pin "1") (pinfunction "1_1") (pintype "passive"))
      (node (ref "J1") (pin "8") (pinfunction "CGND_8") (pintype "passive"))
    )
    (net (code "78") (name "RJ45_FE_1") (class "Default")
      (node (ref "C30") (pin "1") (pinfunction "1_1") (pintype "passive"))
      (node (ref "J3") (pin "8") (pinfunction "CGND_8") (pintype "passive"))
    )
    (net (code "79") (name "RJ45_FE_2") (class "Default")
      (node (ref "C19") (pin "1") (pinfunction "1_1") (pintype "passive"))
      (node (ref "J2") (pin "8") (pinfunction "CGND_8") (pintype "passive"))
    )
    (net (code "80") (name "RJ45_FE_3") (class "Default")
      (node (ref "C31") (pin "1") (pinfunction "1_1") (pintype "passive"))
      (node (ref "J4") (pin "8") (pinfunction "CGND_8") (pintype "passive"))
    )
    (net (code "81") (name "unconnected-(J1-NC-Pad7)") (class "Default")
      (node (ref "J1") (pin "7") (pinfunction "NC_7") (pintype "passive+no_connect"))
    )
    (net (code "82") (name "unconnected-(J2-NC-Pad7)") (class "Default")
      (node (ref "J2") (pin "7") (pinfunction "NC_7") (pintype "passive+no_connect"))
    )
    (net (code "83") (name "unconnected-(J3-NC-Pad7)") (class "Default")
      (node (ref "J3") (pin "7") (pinfunction "NC_7") (pintype "passive+no_connect"))
    )
    (net (code "84") (name "unconnected-(J4-NC-Pad7)") (class "Default")
      (node (ref "J4") (pin "7") (pinfunction "NC_7") (pintype "passive+no_connect"))
    )
    (net (code "85") (name "unconnected-(TVS1-VCC-Pad5)") (class "Default")
      (node (ref "TVS1") (pin "5") (pinfunction "VCC_5") (pintype "power_in+no_connect"))
    )
    (net (code "86") (name "unconnected-(TVS2-VCC-Pad5)") (class "Default")
      (node (ref "TVS2") (pin "5") (pinfunction "VCC_5") (pintype "power_in+no_connect"))
    )
    (net (code "87") (name "unconnected-(TVS3-VCC-Pad5)") (class "Default")
      (node (ref "TVS3") (pin "5") (pinfunction "VCC_5") (pintype "power_in+no_connect"))
    )
    (net (code "88") (name "unconnected-(TVS4-VCC-Pad5)") (class "Default")
      (node (ref "TVS4") (pin "5") (pinfunction "VCC_5") (pintype "power_in+no_connect"))
    )
    (net (code "89") (name "unconnected-(U3-ATST-Pad75)") (class "Default")
      (node (ref "U3") (pin "75") (pinfunction "ATST_75") (pintype "passive+no_connect"))
    )
    (net (code "90") (name "unconnected-(U3-COL5-Pad54)") (class "Default")
      (node (ref "U3") (pin "54") (pinfunction "COL5_54") (pintype "passive+no_connect"))
    )
    (net (code "91") (name "unconnected-(U3-CRS5-Pad53)") (class "Default")
      (node (ref "U3") (pin "53") (pinfunction "CRS5_53") (pintype "passive+no_connect"))
    )
    (net (code "92") (name "unconnected-(U3-NC-Pad22)") (class "Default")
      (node (ref "U3") (pin "22") (pinfunction "NC_22") (pintype "passive+no_connect"))
    )
    (net (code "93") (name "unconnected-(U3-NC-Pad74)") (class "Default")
      (node (ref "U3") (pin "74") (pinfunction "NC_74") (pintype "passive+no_connect"))
    )
    (net (code "94") (name "unconnected-(U3-REFCLKO-Pad55)") (class "Default")
      (node (ref "U3") (pin "55") (pinfunction "REFCLKO_55") (pintype "passive+no_connect"))
    )
    (net (code "95") (name "unconnected-(U3-RXD5_4-Pad57)") (class "Default")
      (node (ref "U3") (pin "57") (pinfunction "RXD5_4_57") (pintype "passive+no_connect"))
    )
    (net (code "96") (name "unconnected-(U3-RXD5_5-Pad58)") (class "Default")
      (node (ref "U3") (pin "58") (pinfunction "RXD5_5_58") (pintype "passive+no_connect"))
    )
    (net (code "97") (name "unconnected-(U3-RXD5_6-Pad59)") (class "Default")
      (node (ref "U3") (pin "59") (pinfunction "RXD5_6_59") (pintype "passive+no_connect"))
    )
    (net (code "98") (name "unconnected-(U3-RXD5_7-Pad60)") (class "Default")
      (node (ref "U3") (pin "60") (pinfunction "RXD5_7_60") (pintype "passive+no_connect"))
    )
    (net (code "99") (name "unconnected-(U3-RXER5-Pad52)") (class "Default")
      (node (ref "U3") (pin "52") (pinfunction "RXER5_52") (pintype "passive+no_connect"))
    )
    (net (code "100") (name "unconnected-(U3-TXD5_4-Pad38)") (class "Default")
      (node (ref "U3") (pin "38") (pinfunction "TXD5_4_38") (pintype "passive+no_connect"))
    )
    (net (code "101") (name "unconnected-(U3-TXD5_5-Pad39)") (class "Default")
      (node (ref "U3") (pin "39") (pinfunction "TXD5_5_39") (pintype "passive+no_connect"))
    )
    (net (code "102") (name "unconnected-(U3-TXD5_6-Pad40)") (class "Default")
      (node (ref "U3") (pin "40") (pinfunction "TXD5_6_40") (pintype "passive+no_connect"))
    )
    (net (code "103") (name "unconnected-(U3-TXD5_7-Pad41)") (class "Default")
      (node (ref "U3") (pin "41") (pinfunction "TXD5_7_41") (pintype "passive+no_connect"))
    )
    (net (code "104") (name "unconnected-(U3-TXER5-Pad37)") (class "Default")
      (node (ref "U3") (pin "37") (pinfunction "TXER5_37") (pintype "passive+no_connect"))
    )
  )
)
